# Pedal_Power.net
KiCad netlist of a schematic drawn in Altium Designer
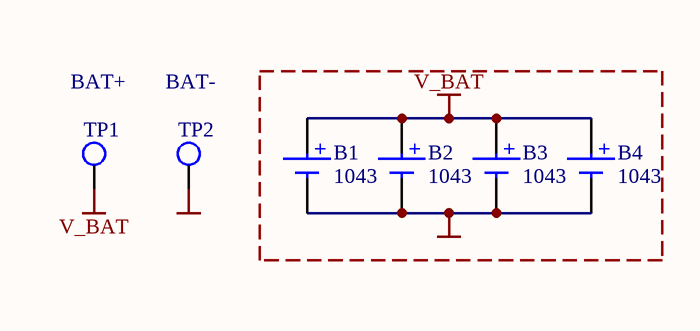
[diagram p0: Pedal_Power.SchDoc]

(export (version "E")
  (design (tool "Eeschema 10.0.6"))
  (components
    (comp (ref "B1")
      (value "1043")
      (footprint "KEYSTONE 1043")
      (description "BATTERY HOLDER 18650 PC PIN")
      (fields (field (name "MANUFACTURER") "Keystone Electronics"))
      (libsource (lib "Celestial Altium Library - altium_library") (part "Keystone 1043"))
    )
    (comp (ref "B2")
      (value "1043")
      (footprint "KEYSTONE 1043")
      (description "BATTERY HOLDER 18650 PC PIN")
      (fields (field (name "MANUFACTURER") "Keystone Electronics"))
      (libsource (lib "Celestial Altium Library - altium_library") (part "Keystone 1043"))
    )
    (comp (ref "B3")
      (value "1043")
      (footprint "KEYSTONE 1043")
      (description "BATTERY HOLDER 18650 PC PIN")
      (fields (field (name "MANUFACTURER") "Keystone Electronics"))
      (libsource (lib "Celestial Altium Library - altium_library") (part "Keystone 1043"))
    )
    (comp (ref "B4")
      (value "1043")
      (footprint "KEYSTONE 1043")
      (description "BATTERY HOLDER 18650 PC PIN")
      (fields (field (name "MANUFACTURER") "Keystone Electronics"))
      (libsource (lib "Celestial Altium Library - altium_library") (part "Keystone 1043"))
    )
    (comp (ref "TP1")
      (value "BAT+")
      (footprint "ProtoStack_H750VBT:TESTPOINT_PAD")
      (libsource (lib "ProtoStack_H750VBT") (part "TestPoint"))
    )
    (comp (ref "TP2")
      (value "BAT-")
      (footprint "ProtoStack_H750VBT:TESTPOINT_PAD")
      (libsource (lib "ProtoStack_H750VBT") (part "TestPoint"))
    )
  )
  (nets
    (net (code "1") (name "GND") (class "Default")
      (node (ref "B1") (pin "2") (pinfunction "-_2") (pintype "passive"))
      (node (ref "B2") (pin "2") (pinfunction "-_2") (pintype "passive"))
      (node (ref "B3") (pin "2") (pinfunction "-_2") (pintype "passive"))
      (node (ref "B4") (pin "2") (pinfunction "-_2") (pintype "passive"))
      (node (ref "TP2") (pin "1") (pinfunction "12_1") (pintype "passive"))
    )
    (net (code "2") (name "V_BAT") (class "Default")
      (node (ref "B1") (pin "1") (pinfunction "+_1") (pintype "passive"))
      (node (ref "B2") (pin "1") (pinfunction "+_1") (pintype "passive"))
      (node (ref "B3") (pin "1") (pinfunction "+_1") (pintype "passive"))
      (node (ref "B4") (pin "1") (pinfunction "+_1") (pintype "passive"))
      (node (ref "TP1") (pin "1") (pinfunction "12_1") (pintype "passive"))
    )
  )
)
